# PCB_2c.net
KiCad netlist of a schematic drawn in EAGLE
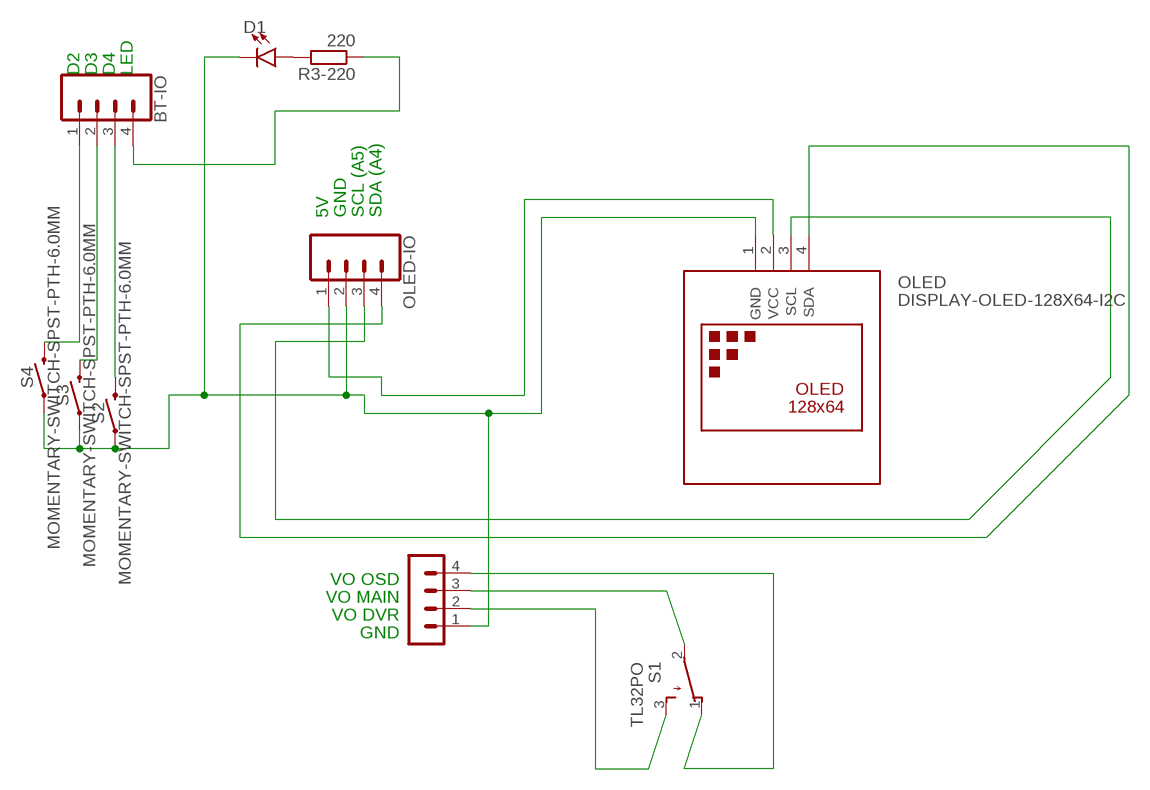
[diagram p0: schematic, sheet 1]

(export (version "E")
  (design (tool "Eeschema 10.0.6"))
  (components
    (comp (ref "BT-IO")
      (value "CONN_04")
      (footprint "eagle-import:1X04")
      (libsource (lib "eagle-import") (part "CONN_04"))
    )
    (comp (ref "D1")
      (value "LED3MM")
      (footprint "eagle-import:LED_3MM")
      (libsource (lib "eagle-import") (part "LED3MM"))
    )
    (comp (ref "IO3")
      (value "MA04-1")
      (footprint "eagle-import:MA04-1")
      (libsource (lib "eagle-import") (part "MA04-1"))
    )
    (comp (ref "OLED")
      (value "DISPLAY-OLED-128X64-I2C")
      (footprint "eagle-import:DISPLAY-OLED-128X64-I2C")
      (libsource (lib "eagle-import") (part "DISPLAY-OLED-128X64-I2C"))
    )
    (comp (ref "OLED-IO")
      (value "CONN_04")
      (footprint "eagle-import:1X04")
      (libsource (lib "eagle-import") (part "CONN_04"))
    )
    (comp (ref "R3-220")
      (value "220")
      (footprint "eagle-import:R1206")
      (libsource (lib "eagle-import") (part "R-EU_R1206"))
    )
    (comp (ref "S1")
      (value "TL32PO")
      (footprint "eagle-import:TL3XPO")
      (libsource (lib "eagle-import") (part "TL32PO"))
    )
    (comp (ref "S2")
      (value "MOMENTARY-SWITCH-SPST-PTH-6.0MM")
      (footprint "eagle-import:TACTILE_SWITCH_PTH_6.0MM")
      (libsource (lib "eagle-import") (part "MOMENTARY-SWITCH-SPST-PTH-6.0MM"))
    )
    (comp (ref "S3")
      (value "MOMENTARY-SWITCH-SPST-PTH-6.0MM")
      (footprint "eagle-import:TACTILE_SWITCH_PTH_6.0MM")
      (libsource (lib "eagle-import") (part "MOMENTARY-SWITCH-SPST-PTH-6.0MM"))
    )
    (comp (ref "S4")
      (value "MOMENTARY-SWITCH-SPST-PTH-6.0MM")
      (footprint "eagle-import:TACTILE_SWITCH_PTH_6.0MM")
      (libsource (lib "eagle-import") (part "MOMENTARY-SWITCH-SPST-PTH-6.0MM"))
    )
  )
  (nets
    (net (code "1") (name "Net-(BT-IO-Pad4)") (class "Default")
      (node (ref "BT-IO") (pin "4") (pinfunction "4_4") (pintype "passive"))
      (node (ref "R3-220") (pin "1") (pinfunction "1_1") (pintype "passive"))
    )
    (net (code "2") (name "Net-(D1-C)") (class "Default")
      (node (ref "D1") (pin "K") (pinfunction "C_K") (pintype "passive"))
      (node (ref "IO3") (pin "1") (pinfunction "1_1") (pintype "passive"))
      (node (ref "OLED") (pin "1") (pinfunction "GND_1") (pintype "power_in"))
      (node (ref "OLED-IO") (pin "2") (pinfunction "2_2") (pintype "passive"))
      (node (ref "S2") (pin "1") (pinfunction "1_1") (pintype "passive"))
      (node (ref "S3") (pin "1") (pinfunction "1_1") (pintype "passive"))
      (node (ref "S4") (pin "1") (pinfunction "1_1") (pintype "passive"))
    )
    (net (code "3") (name "Net-(D1-PadA)") (class "Default")
      (node (ref "D1") (pin "A") (pinfunction "A_A") (pintype "passive"))
      (node (ref "R3-220") (pin "2") (pinfunction "2_2") (pintype "passive"))
    )
    (net (code "4") (name "Net-(OLED-SCL)") (class "Default")
      (node (ref "OLED") (pin "3") (pinfunction "SCL_3") (pintype "bidirectional"))
      (node (ref "OLED-IO") (pin "3") (pinfunction "3_3") (pintype "passive"))
    )
    (net (code "5") (name "Net-(OLED-SDA)") (class "Default")
      (node (ref "OLED") (pin "4") (pinfunction "SDA_4") (pintype "bidirectional"))
      (node (ref "OLED-IO") (pin "4") (pinfunction "4_4") (pintype "passive"))
    )
    (net (code "6") (name "Net-(OLED-VCC)") (class "Default")
      (node (ref "OLED") (pin "2") (pinfunction "VCC_2") (pintype "power_in"))
      (node (ref "OLED-IO") (pin "1") (pinfunction "1_1") (pintype "passive"))
    )
    (net (code "7") (name "Net-(S1-O)") (class "Default")
      (node (ref "IO3") (pin "4") (pinfunction "4_4") (pintype "passive"))
      (node (ref "S1") (pin "1") (pinfunction "O_1") (pintype "passive"))
    )
    (net (code "8") (name "Net-(S1-P)") (class "Default")
      (node (ref "IO3") (pin "3") (pinfunction "3_3") (pintype "passive"))
      (node (ref "S1") (pin "2") (pinfunction "P_2") (pintype "passive"))
    )
    (net (code "9") (name "Net-(S1-S)") (class "Default")
      (node (ref "IO3") (pin "2") (pinfunction "2_2") (pintype "passive"))
      (node (ref "S1") (pin "3") (pinfunction "S_3") (pintype "passive"))
    )
    (net (code "10") (name "Net-(S2-2)") (class "Default")
      (node (ref "BT-IO") (pin "3") (pinfunction "3_3") (pintype "passive"))
      (node (ref "S2") (pin "3") (pinfunction "2_3") (pintype "passive"))
    )
    (net (code "11") (name "Net-(S3-2)") (class "Default")
      (node (ref "BT-IO") (pin "2") (pinfunction "2_2") (pintype "passive"))
      (node (ref "S3") (pin "3") (pinfunction "2_3") (pintype "passive"))
    )
    (net (code "12") (name "Net-(S4-2)") (class "Default")
      (node (ref "BT-IO") (pin "1") (pinfunction "1_1") (pintype "passive"))
      (node (ref "S4") (pin "3") (pinfunction "2_3") (pintype "passive"))
    )
  )
)
